# 6inch_mipi_V1_0.net
KiCad netlist of a schematic drawn in Altium Designer
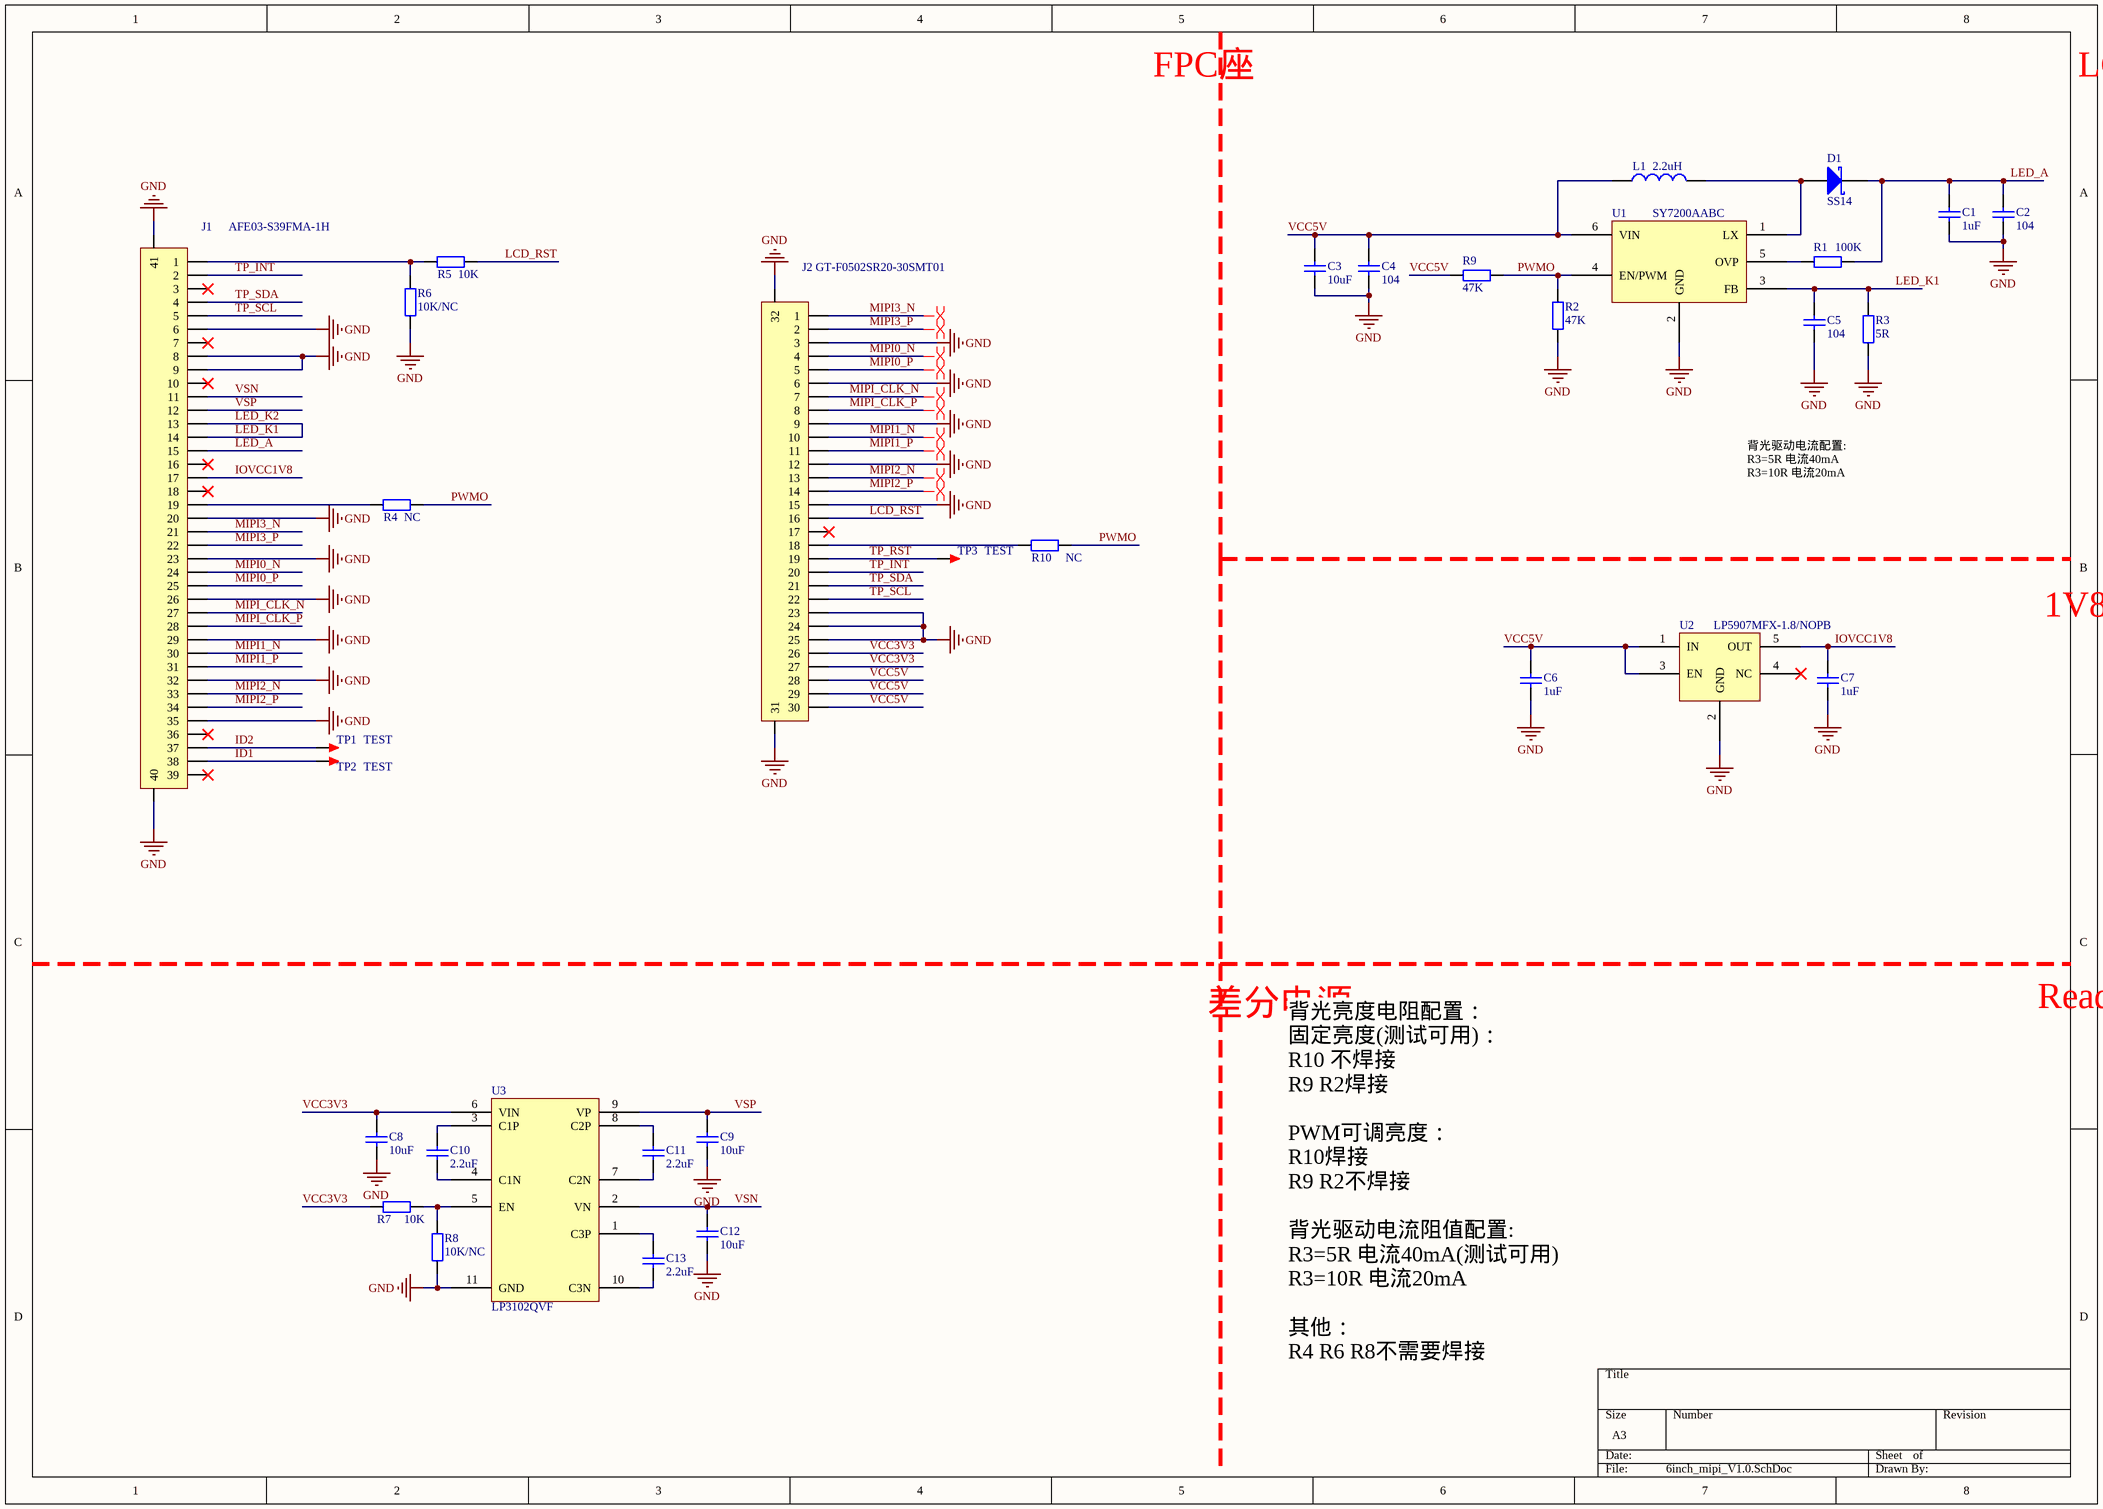
[diagram p0: 6inch_mipi_V1.0.SchDoc]

(export (version "E")
  (design (tool "Eeschema 10.0.6"))
  (components
    (comp (ref "C1")
      (value "1uF")
      (footprint "C0402_L")
      (description "贴片电容/MLCC电容")
      (libsource (lib "0.1 - 电阻-电容-电感-晶振-晶体-磁珠-电位器-法拉电容-馈通电容") (part "C"))
    )
    (comp (ref "C2")
      (value "104")
      (footprint "C0402_L")
      (description "贴片电容/MLCC电容")
      (libsource (lib "0.1 - 电阻-电容-电感-晶振-晶体-磁珠-电位器-法拉电容-馈通电容") (part "C"))
    )
    (comp (ref "C3")
      (value "10uF")
      (footprint "C0402_L")
      (description "贴片电容/MLCC电容")
      (libsource (lib "0.1 - 电阻-电容-电感-晶振-晶体-磁珠-电位器-法拉电容-馈通电容") (part "C"))
    )
    (comp (ref "C4")
      (value "104")
      (footprint "C0402_L")
      (description "贴片电容/MLCC电容")
      (libsource (lib "0.1 - 电阻-电容-电感-晶振-晶体-磁珠-电位器-法拉电容-馈通电容") (part "C"))
    )
    (comp (ref "C5")
      (value "104")
      (footprint "C0402_L")
      (description "贴片电容/MLCC电容")
      (libsource (lib "0.1 - 电阻-电容-电感-晶振-晶体-磁珠-电位器-法拉电容-馈通电容") (part "C"))
    )
    (comp (ref "C6")
      (value "1uF")
      (footprint "C0402_L")
      (description "贴片电容/MLCC电容")
      (libsource (lib "0.1 - 电阻-电容-电感-晶振-晶体-磁珠-电位器-法拉电容-馈通电容") (part "C"))
    )
    (comp (ref "C7")
      (value "1uF")
      (footprint "C0402_L")
      (description "贴片电容/MLCC电容")
      (libsource (lib "0.1 - 电阻-电容-电感-晶振-晶体-磁珠-电位器-法拉电容-馈通电容") (part "C"))
    )
    (comp (ref "C8")
      (value "10uF")
      (footprint "C0402_L")
      (description "贴片电容/MLCC电容")
      (libsource (lib "0.1 - 电阻-电容-电感-晶振-晶体-磁珠-电位器-法拉电容-馈通电容") (part "C"))
    )
    (comp (ref "C9")
      (value "10uF")
      (footprint "C0402_L")
      (description "贴片电容/MLCC电容")
      (libsource (lib "0.1 - 电阻-电容-电感-晶振-晶体-磁珠-电位器-法拉电容-馈通电容") (part "C"))
    )
    (comp (ref "C10")
      (value "2.2uF")
      (footprint "C0402_L")
      (description "贴片电容/MLCC电容")
      (libsource (lib "0.1 - 电阻-电容-电感-晶振-晶体-磁珠-电位器-法拉电容-馈通电容") (part "C"))
    )
    (comp (ref "C11")
      (value "2.2uF")
      (footprint "C0402_L")
      (description "贴片电容/MLCC电容")
      (libsource (lib "0.1 - 电阻-电容-电感-晶振-晶体-磁珠-电位器-法拉电容-馈通电容") (part "C"))
    )
    (comp (ref "C12")
      (value "10uF")
      (footprint "C0402_L")
      (description "贴片电容/MLCC电容")
      (libsource (lib "0.1 - 电阻-电容-电感-晶振-晶体-磁珠-电位器-法拉电容-馈通电容") (part "C"))
    )
    (comp (ref "C13")
      (value "2.2uF")
      (footprint "C0402_L")
      (description "贴片电容/MLCC电容")
      (libsource (lib "0.1 - 电阻-电容-电感-晶振-晶体-磁珠-电位器-法拉电容-馈通电容") (part "C"))
    )
    (comp (ref "D1")
      (value "SS14")
      (footprint "SOD-123F")
      (description "肖特基二极管")
      (libsource (lib "0.2 - 二极管-TVS-ESD-整流桥-放电管") (part "SS14"))
    )
    (comp (ref "J1")
      (value "AFE03-S39FMA-1H")
      (footprint "FPC-SMD_P0.30-39P_FGS-XJ-H1.0")
      (description "FPC座下接 0.3mm 39P")
      (libsource (lib "个人库") (part "AFE03-S39FMA-1H"))
    )
    (comp (ref "J2")
      (value "GT-F0502SR20-30SMT01")
      (footprint "FPC-SMD_30P-P0.50_GT-F0502SR20-30SMT01")
      (description "FPC座下接 0.5mm 30P")
      (libsource (lib "个人库") (part "GT-F0502SR20-30SMT01"))
    )
    (comp (ref "L1")
      (value "2.2uH")
      (footprint "L-SMD-0420")
      (description "贴片小功率电感")
      (libsource (lib "0.1 - 电阻-电容-电感-晶振-晶体-磁珠-电位器-法拉电容-馈通电容") (part "L"))
    )
    (comp (ref "R1")
      (value "100K")
      (footprint "R0402_L")
      (description "贴片电阻")
      (libsource (lib "0.1 - 电阻-电容-电感-晶振-晶体-磁珠-电位器-法拉电容-馈通电容") (part "R"))
    )
    (comp (ref "R2")
      (value "47K")
      (footprint "R0402_L")
      (description "贴片电阻")
      (libsource (lib "0.1 - 电阻-电容-电感-晶振-晶体-磁珠-电位器-法拉电容-馈通电容") (part "R"))
    )
    (comp (ref "R3")
      (value "5R")
      (footprint "R0402_L")
      (description "贴片电阻")
      (libsource (lib "0.1 - 电阻-电容-电感-晶振-晶体-磁珠-电位器-法拉电容-馈通电容") (part "R"))
    )
    (comp (ref "R4")
      (value "NC")
      (footprint "R0402_L")
      (description "贴片电阻")
      (libsource (lib "0.1 - 电阻-电容-电感-晶振-晶体-磁珠-电位器-法拉电容-馈通电容") (part "R"))
    )
    (comp (ref "R5")
      (value "10K")
      (footprint "R0402_L")
      (description "贴片电阻")
      (libsource (lib "0.1 - 电阻-电容-电感-晶振-晶体-磁珠-电位器-法拉电容-馈通电容") (part "R"))
    )
    (comp (ref "R6")
      (value "10K/NC")
      (footprint "R0402_L")
      (description "贴片电阻")
      (libsource (lib "0.1 - 电阻-电容-电感-晶振-晶体-磁珠-电位器-法拉电容-馈通电容") (part "R"))
    )
    (comp (ref "R7")
      (value "10K")
      (footprint "R0402_L")
      (description "贴片电阻")
      (libsource (lib "0.1 - 电阻-电容-电感-晶振-晶体-磁珠-电位器-法拉电容-馈通电容") (part "R"))
    )
    (comp (ref "R8")
      (value "10K/NC")
      (footprint "R0402_L")
      (description "贴片电阻")
      (libsource (lib "0.1 - 电阻-电容-电感-晶振-晶体-磁珠-电位器-法拉电容-馈通电容") (part "R"))
    )
    (comp (ref "R9")
      (value "47K")
      (footprint "R0402_L")
      (description "贴片电阻")
      (libsource (lib "0.1 - 电阻-电容-电感-晶振-晶体-磁珠-电位器-法拉电容-馈通电容") (part "R"))
    )
    (comp (ref "R10")
      (value "NC")
      (footprint "R0402_L")
      (description "贴片电阻")
      (libsource (lib "0.1 - 电阻-电容-电感-晶振-晶体-磁珠-电位器-法拉电容-馈通电容") (part "R"))
    )
    (comp (ref "TP1")
      (value "TEST")
      (footprint "TEST 1.6")
      (description "测试点")
      (libsource (lib "0.5 - 按键_开关_蜂鸣器_保险丝_电池_测试点_Mark点_铜柱") (part "TEST"))
    )
    (comp (ref "TP2")
      (value "TEST")
      (footprint "TEST 1.6")
      (description "测试点")
      (libsource (lib "0.5 - 按键_开关_蜂鸣器_保险丝_电池_测试点_Mark点_铜柱") (part "TEST"))
    )
    (comp (ref "TP3")
      (value "TEST")
      (footprint "TEST 1.6")
      (description "测试点")
      (libsource (lib "0.5 - 按键_开关_蜂鸣器_保险丝_电池_测试点_Mark点_铜柱") (part "TEST"))
    )
    (comp (ref "U1")
      (value "SY7200AABC")
      (footprint "SOT23-6")
      (description "30V 2A LED驱动芯片")
      (libsource (lib "个人库") (part "SY7200AABC"))
    )
    (comp (ref "U2")
      (value "LP5907MFX-1.8/NOPB")
      (footprint "SOT23-5")
      (description "1.8V LDO芯片")
      (libsource (lib "个人库") (part "LP5907MFX-1.8/NOPB"))
    )
    (comp (ref "U3")
      (value "LP3102QVF")
      (footprint "TDFN-10_L3.0-W3.0-P0.50-BL-EP")
      (description "双路电荷泵DC/DC")
      (libsource (lib "个人库") (part "LP3102QVF"))
    )
  )
  (nets
    (net (code "1") (name "/ID1") (class "Default")
      (node (ref "J1") (pin "38") (pinfunction "38_38") (pintype "passive"))
      (node (ref "TP2") (pin "1") (pinfunction "1_1") (pintype "passive"))
    )
    (net (code "2") (name "/ID2") (class "Default")
      (node (ref "J1") (pin "37") (pinfunction "37_37") (pintype "passive"))
      (node (ref "TP1") (pin "1") (pinfunction "1_1") (pintype "passive"))
    )
    (net (code "3") (name "/IOVCC1V8") (class "Default")
      (node (ref "C7") (pin "2") (pinfunction "2_2") (pintype "passive"))
      (node (ref "J1") (pin "17") (pinfunction "17_17") (pintype "passive"))
      (node (ref "U2") (pin "5") (pinfunction "OUT_5") (pintype "passive"))
    )
    (net (code "4") (name "/LCD_RST") (class "Default")
      (node (ref "J2") (pin "16") (pinfunction "16_16") (pintype "passive"))
      (node (ref "R5") (pin "1") (pinfunction "1_1") (pintype "passive"))
    )
    (net (code "5") (name "/LED_A") (class "Default")
      (node (ref "C1") (pin "2") (pinfunction "2_2") (pintype "passive"))
      (node (ref "C2") (pin "2") (pinfunction "2_2") (pintype "passive"))
      (node (ref "D1") (pin "2") (pinfunction "K_2") (pintype "passive"))
      (node (ref "J1") (pin "15") (pinfunction "15_15") (pintype "passive"))
      (node (ref "R1") (pin "2") (pinfunction "2_2") (pintype "passive"))
    )
    (net (code "6") (name "/LED_K1") (class "Default")
      (node (ref "C5") (pin "2") (pinfunction "2_2") (pintype "passive"))
      (node (ref "J1") (pin "13") (pinfunction "13_13") (pintype "passive"))
      (node (ref "J1") (pin "14") (pinfunction "14_14") (pintype "passive"))
      (node (ref "R3") (pin "2") (pinfunction "2_2") (pintype "passive"))
      (node (ref "U1") (pin "3") (pinfunction "FB_3") (pintype "passive"))
    )
    (net (code "7") (name "/MIPI0_N") (class "Default")
      (node (ref "J1") (pin "24") (pinfunction "24_24") (pintype "passive"))
      (node (ref "J2") (pin "4") (pinfunction "4_4") (pintype "passive"))
    )
    (net (code "8") (name "/MIPI0_P") (class "Default")
      (node (ref "J1") (pin "25") (pinfunction "25_25") (pintype "passive"))
      (node (ref "J2") (pin "5") (pinfunction "5_5") (pintype "passive"))
    )
    (net (code "9") (name "/MIPI1_N") (class "Default")
      (node (ref "J1") (pin "30") (pinfunction "30_30") (pintype "passive"))
      (node (ref "J2") (pin "10") (pinfunction "10_10") (pintype "passive"))
    )
    (net (code "10") (name "/MIPI1_P") (class "Default")
      (node (ref "J1") (pin "31") (pinfunction "31_31") (pintype "passive"))
      (node (ref "J2") (pin "11") (pinfunction "11_11") (pintype "passive"))
    )
    (net (code "11") (name "/MIPI2_N") (class "Default")
      (node (ref "J1") (pin "33") (pinfunction "33_33") (pintype "passive"))
      (node (ref "J2") (pin "13") (pinfunction "13_13") (pintype "passive"))
    )
    (net (code "12") (name "/MIPI2_P") (class "Default")
      (node (ref "J1") (pin "34") (pinfunction "34_34") (pintype "passive"))
      (node (ref "J2") (pin "14") (pinfunction "14_14") (pintype "passive"))
    )
    (net (code "13") (name "/MIPI3_N") (class "Default")
      (node (ref "J1") (pin "21") (pinfunction "21_21") (pintype "passive"))
      (node (ref "J2") (pin "1") (pinfunction "1_1") (pintype "passive"))
    )
    (net (code "14") (name "/MIPI3_P") (class "Default")
      (node (ref "J1") (pin "22") (pinfunction "22_22") (pintype "passive"))
      (node (ref "J2") (pin "2") (pinfunction "2_2") (pintype "passive"))
    )
    (net (code "15") (name "/MIPI_CLK_N") (class "Default")
      (node (ref "J1") (pin "27") (pinfunction "27_27") (pintype "passive"))
      (node (ref "J2") (pin "7") (pinfunction "7_7") (pintype "passive"))
    )
    (net (code "16") (name "/MIPI_CLK_P") (class "Default")
      (node (ref "J1") (pin "28") (pinfunction "28_28") (pintype "passive"))
      (node (ref "J2") (pin "8") (pinfunction "8_8") (pintype "passive"))
    )
    (net (code "17") (name "/PWMO") (class "Default")
      (node (ref "R10") (pin "1") (pinfunction "1_1") (pintype "passive"))
      (node (ref "R2") (pin "1") (pinfunction "1_1") (pintype "passive"))
      (node (ref "R4") (pin "1") (pinfunction "1_1") (pintype "passive"))
      (node (ref "R9") (pin "2") (pinfunction "2_2") (pintype "passive"))
      (node (ref "U1") (pin "4") (pinfunction "EN/PWM_4") (pintype "passive"))
    )
    (net (code "18") (name "/TP_INT") (class "Default")
      (node (ref "J1") (pin "2") (pinfunction "2_2") (pintype "passive"))
      (node (ref "J2") (pin "20") (pinfunction "20_20") (pintype "passive"))
    )
    (net (code "19") (name "/TP_RST") (class "Default")
      (node (ref "J2") (pin "19") (pinfunction "19_19") (pintype "passive"))
      (node (ref "TP3") (pin "1") (pinfunction "1_1") (pintype "passive"))
    )
    (net (code "20") (name "/TP_SCL") (class "Default")
      (node (ref "J1") (pin "5") (pinfunction "5_5") (pintype "passive"))
      (node (ref "J2") (pin "22") (pinfunction "22_22") (pintype "passive"))
    )
    (net (code "21") (name "/TP_SDA") (class "Default")
      (node (ref "J1") (pin "4") (pinfunction "4_4") (pintype "passive"))
      (node (ref "J2") (pin "21") (pinfunction "21_21") (pintype "passive"))
    )
    (net (code "22") (name "/VCC3V3") (class "Default")
      (node (ref "C8") (pin "2") (pinfunction "2_2") (pintype "passive"))
      (node (ref "J2") (pin "26") (pinfunction "26_26") (pintype "passive"))
      (node (ref "J2") (pin "27") (pinfunction "27_27") (pintype "passive"))
      (node (ref "R7") (pin "1") (pinfunction "1_1") (pintype "passive"))
      (node (ref "U3") (pin "6") (pinfunction "VIN_6") (pintype "passive"))
    )
    (net (code "23") (name "/VCC5V") (class "Default")
      (node (ref "C3") (pin "2") (pinfunction "2_2") (pintype "passive"))
      (node (ref "C4") (pin "2") (pinfunction "2_2") (pintype "passive"))
      (node (ref "C6") (pin "2") (pinfunction "2_2") (pintype "passive"))
      (node (ref "J2") (pin "28") (pinfunction "28_28") (pintype "passive"))
      (node (ref "J2") (pin "29") (pinfunction "29_29") (pintype "passive"))
      (node (ref "J2") (pin "30") (pinfunction "30_30") (pintype "passive"))
      (node (ref "L1") (pin "1") (pinfunction "1_1") (pintype "passive"))
      (node (ref "R9") (pin "1") (pinfunction "1_1") (pintype "passive"))
      (node (ref "U1") (pin "6") (pinfunction "VIN_6") (pintype "passive"))
      (node (ref "U2") (pin "1") (pinfunction "IN_1") (pintype "passive"))
      (node (ref "U2") (pin "3") (pinfunction "EN_3") (pintype "passive"))
    )
    (net (code "24") (name "/VSN") (class "Default")
      (node (ref "C12") (pin "2") (pinfunction "2_2") (pintype "passive"))
      (node (ref "J1") (pin "11") (pinfunction "11_11") (pintype "passive"))
      (node (ref "U3") (pin "2") (pinfunction "VN_2") (pintype "passive"))
    )
    (net (code "25") (name "/VSP") (class "Default")
      (node (ref "C9") (pin "2") (pinfunction "2_2") (pintype "passive"))
      (node (ref "J1") (pin "12") (pinfunction "12_12") (pintype "passive"))
      (node (ref "U3") (pin "9") (pinfunction "VP_9") (pintype "passive"))
    )
    (net (code "26") (name "GND") (class "Default")
      (node (ref "C1") (pin "1") (pinfunction "1_1") (pintype "passive"))
      (node (ref "C12") (pin "1") (pinfunction "1_1") (pintype "passive"))
      (node (ref "C2") (pin "1") (pinfunction "1_1") (pintype "passive"))
      (node (ref "C3") (pin "1") (pinfunction "1_1") (pintype "passive"))
      (node (ref "C4") (pin "1") (pinfunction "1_1") (pintype "passive"))
      (node (ref "C5") (pin "1") (pinfunction "1_1") (pintype "passive"))
      (node (ref "C6") (pin "1") (pinfunction "1_1") (pintype "passive"))
      (node (ref "C7") (pin "1") (pinfunction "1_1") (pintype "passive"))
      (node (ref "C8") (pin "1") (pinfunction "1_1") (pintype "passive"))
      (node (ref "C9") (pin "1") (pinfunction "1_1") (pintype "passive"))
      (node (ref "J1") (pin "20") (pinfunction "20_20") (pintype "passive"))
      (node (ref "J1") (pin "23") (pinfunction "23_23") (pintype "passive"))
      (node (ref "J1") (pin "26") (pinfunction "26_26") (pintype "passive"))
      (node (ref "J1") (pin "29") (pinfunction "29_29") (pintype "passive"))
      (node (ref "J1") (pin "32") (pinfunction "32_32") (pintype "passive"))
      (node (ref "J1") (pin "35") (pinfunction "35_35") (pintype "passive"))
      (node (ref "J1") (pin "40") (pinfunction "40_40") (pintype "passive"))
      (node (ref "J1") (pin "41") (pinfunction "41_41") (pintype "passive"))
      (node (ref "J1") (pin "6") (pinfunction "6_6") (pintype "passive"))
      (node (ref "J1") (pin "8") (pinfunction "8_8") (pintype "passive"))
      (node (ref "J1") (pin "9") (pinfunction "9_9") (pintype "passive"))
      (node (ref "J2") (pin "12") (pinfunction "12_12") (pintype "passive"))
      (node (ref "J2") (pin "15") (pinfunction "15_15") (pintype "passive"))
      (node (ref "J2") (pin "23") (pinfunction "23_23") (pintype "passive"))
      (node (ref "J2") (pin "24") (pinfunction "24_24") (pintype "passive"))
      (node (ref "J2") (pin "25") (pinfunction "25_25") (pintype "passive"))
      (node (ref "J2") (pin "3") (pinfunction "3_3") (pintype "passive"))
      (node (ref "J2") (pin "31") (pinfunction "31_31") (pintype "passive"))
      (node (ref "J2") (pin "32") (pinfunction "32_32") (pintype "passive"))
      (node (ref "J2") (pin "6") (pinfunction "6_6") (pintype "passive"))
      (node (ref "J2") (pin "9") (pinfunction "9_9") (pintype "passive"))
      (node (ref "R2") (pin "2") (pinfunction "2_2") (pintype "passive"))
      (node (ref "R3") (pin "1") (pinfunction "1_1") (pintype "passive"))
      (node (ref "R6") (pin "2") (pinfunction "2_2") (pintype "passive"))
      (node (ref "R8") (pin "2") (pinfunction "2_2") (pintype "passive"))
      (node (ref "U1") (pin "2") (pinfunction "GND_2") (pintype "passive"))
      (node (ref "U2") (pin "2") (pinfunction "GND_2") (pintype "passive"))
      (node (ref "U3") (pin "11") (pinfunction "GND_11") (pintype "passive"))
    )
    (net (code "27") (name "Net-(D1-A)") (class "Default")
      (node (ref "D1") (pin "1") (pinfunction "A_1") (pintype "passive"))
      (node (ref "L1") (pin "2") (pinfunction "2_2") (pintype "passive"))
      (node (ref "U1") (pin "1") (pinfunction "LX_1") (pintype "passive"))
    )
    (net (code "28") (name "Net-(J1-Pad1)") (class "Default")
      (node (ref "J1") (pin "1") (pinfunction "1_1") (pintype "passive"))
      (node (ref "R5") (pin "2") (pinfunction "2_2") (pintype "passive"))
      (node (ref "R6") (pin "1") (pinfunction "1_1") (pintype "passive"))
    )
    (net (code "29") (name "Net-(J1-Pad19)") (class "Default")
      (node (ref "J1") (pin "19") (pinfunction "19_19") (pintype "passive"))
      (node (ref "R4") (pin "2") (pinfunction "2_2") (pintype "passive"))
    )
    (net (code "30") (name "Net-(J2-Pad18)") (class "Default")
      (node (ref "J2") (pin "18") (pinfunction "18_18") (pintype "passive"))
      (node (ref "R10") (pin "2") (pinfunction "2_2") (pintype "passive"))
    )
    (net (code "31") (name "Net-(U1-OVP)") (class "Default")
      (node (ref "R1") (pin "1") (pinfunction "1_1") (pintype "passive"))
      (node (ref "U1") (pin "5") (pinfunction "OVP_5") (pintype "passive"))
    )
    (net (code "32") (name "Net-(U3-C1N)") (class "Default")
      (node (ref "C10") (pin "1") (pinfunction "1_1") (pintype "passive"))
      (node (ref "U3") (pin "4") (pinfunction "C1N_4") (pintype "passive"))
    )
    (net (code "33") (name "Net-(U3-C1P)") (class "Default")
      (node (ref "C10") (pin "2") (pinfunction "2_2") (pintype "passive"))
      (node (ref "U3") (pin "3") (pinfunction "C1P_3") (pintype "passive"))
    )
    (net (code "34") (name "Net-(U3-C2N)") (class "Default")
      (node (ref "C11") (pin "1") (pinfunction "1_1") (pintype "passive"))
      (node (ref "U3") (pin "7") (pinfunction "C2N_7") (pintype "passive"))
    )
    (net (code "35") (name "Net-(U3-C2P)") (class "Default")
      (node (ref "C11") (pin "2") (pinfunction "2_2") (pintype "passive"))
      (node (ref "U3") (pin "8") (pinfunction "C2P_8") (pintype "passive"))
    )
    (net (code "36") (name "Net-(U3-C3N)") (class "Default")
      (node (ref "C13") (pin "1") (pinfunction "1_1") (pintype "passive"))
      (node (ref "U3") (pin "10") (pinfunction "C3N_10") (pintype "passive"))
    )
    (net (code "37") (name "Net-(U3-C3P)") (class "Default")
      (node (ref "C13") (pin "2") (pinfunction "2_2") (pintype "passive"))
      (node (ref "U3") (pin "1") (pinfunction "C3P_1") (pintype "passive"))
    )
    (net (code "38") (name "Net-(U3-EN)") (class "Default")
      (node (ref "R7") (pin "2") (pinfunction "2_2") (pintype "passive"))
      (node (ref "R8") (pin "1") (pinfunction "1_1") (pintype "passive"))
      (node (ref "U3") (pin "5") (pinfunction "EN_5") (pintype "passive"))
    )
    (net (code "39") (name "unconnected-(J1-Pad3)") (class "Default")
      (node (ref "J1") (pin "3") (pinfunction "3_3") (pintype "passive+no_connect"))
    )
    (net (code "40") (name "unconnected-(J1-Pad7)") (class "Default")
      (node (ref "J1") (pin "7") (pinfunction "7_7") (pintype "passive+no_connect"))
    )
    (net (code "41") (name "unconnected-(J1-Pad10)") (class "Default")
      (node (ref "J1") (pin "10") (pinfunction "10_10") (pintype "passive+no_connect"))
    )
    (net (code "42") (name "unconnected-(J1-Pad16)") (class "Default")
      (node (ref "J1") (pin "16") (pinfunction "16_16") (pintype "passive+no_connect"))
    )
    (net (code "43") (name "unconnected-(J1-Pad18)") (class "Default")
      (node (ref "J1") (pin "18") (pinfunction "18_18") (pintype "passive+no_connect"))
    )
    (net (code "44") (name "unconnected-(J1-Pad36)") (class "Default")
      (node (ref "J1") (pin "36") (pinfunction "36_36") (pintype "passive+no_connect"))
    )
    (net (code "45") (name "unconnected-(J1-Pad39)") (class "Default")
      (node (ref "J1") (pin "39") (pinfunction "39_39") (pintype "passive+no_connect"))
    )
    (net (code "46") (name "unconnected-(J2-Pad17)") (class "Default")
      (node (ref "J2") (pin "17") (pinfunction "17_17") (pintype "passive+no_connect"))
    )
    (net (code "47") (name "unconnected-(U2-NC-Pad4)") (class "Default")
      (node (ref "U2") (pin "4") (pinfunction "NC_4") (pintype "passive+no_connect"))
    )
  )
)
